# balloon-v02.net
KiCad netlist of a schematic drawn in EAGLE
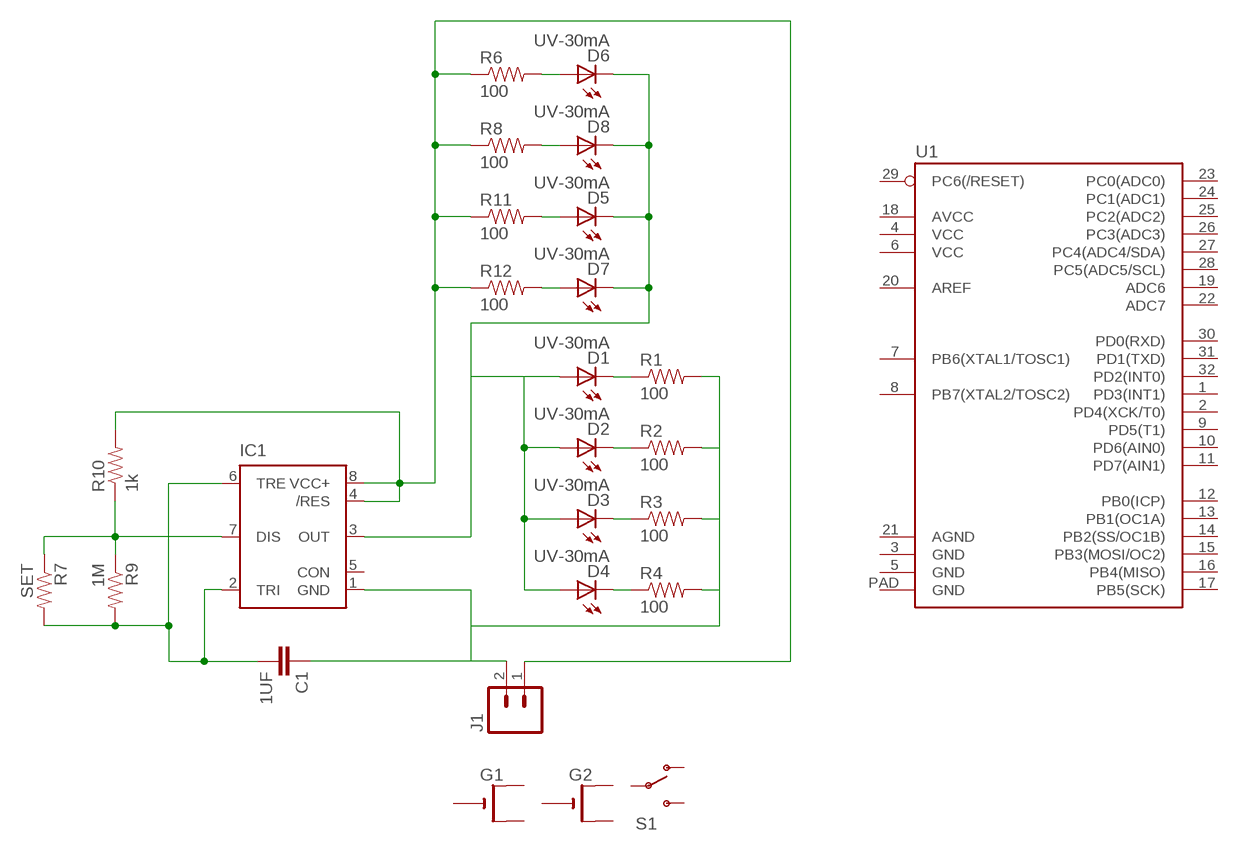
[diagram p0: schematic, sheet 1]

(export (version "E")
  (design (tool "Eeschema 10.0.6"))
  (components
    (comp (ref "C1")
      (value "1UF")
      (footprint "eagle-import:0603-CAP")
      (libsource (lib "eagle-import") (part "CAP0603-CAP"))
    )
    (comp (ref "D1")
      (value "UV-30mA")
      (footprint "eagle-import:CHIPLED_0603")
      (libsource (lib "eagle-import") (part "LEDCHIPLED_0603"))
    )
    (comp (ref "D2")
      (value "UV-30mA")
      (footprint "eagle-import:CHIPLED_0603")
      (libsource (lib "eagle-import") (part "LEDCHIPLED_0603"))
    )
    (comp (ref "D3")
      (value "UV-30mA")
      (footprint "eagle-import:CHIPLED_0603")
      (libsource (lib "eagle-import") (part "LEDCHIPLED_0603"))
    )
    (comp (ref "D4")
      (value "UV-30mA")
      (footprint "eagle-import:CHIPLED_0603")
      (libsource (lib "eagle-import") (part "LEDCHIPLED_0603"))
    )
    (comp (ref "D5")
      (value "UV-30mA")
      (footprint "eagle-import:CHIPLED_0603")
      (libsource (lib "eagle-import") (part "LEDCHIPLED_0603"))
    )
    (comp (ref "D6")
      (value "UV-30mA")
      (footprint "eagle-import:CHIPLED_0603")
      (libsource (lib "eagle-import") (part "LEDCHIPLED_0603"))
    )
    (comp (ref "D7")
      (value "UV-30mA")
      (footprint "eagle-import:CHIPLED_0603")
      (libsource (lib "eagle-import") (part "LEDCHIPLED_0603"))
    )
    (comp (ref "D8")
      (value "UV-30mA")
      (footprint "eagle-import:CHIPLED_0603")
      (libsource (lib "eagle-import") (part "LEDCHIPLED_0603"))
    )
    (comp (ref "G1")
      (value "CR2032SMT")
      (footprint "eagle-import:CR2032-SMD")
      (libsource (lib "eagle-import") (part "CR2032SMT"))
    )
    (comp (ref "G2")
      (value "CR2032SMT")
      (footprint "eagle-import:CR2032-SMD")
      (libsource (lib "eagle-import") (part "CR2032SMT"))
    )
    (comp (ref "IC1")
      (value "NE555D")
      (footprint "eagle-import:SO08")
      (libsource (lib "eagle-import") (part "NE555D"))
    )
    (comp (ref "J1")
      (value "M02PTH3")
      (footprint "eagle-import:1X02_LONGPADS")
      (libsource (lib "eagle-import") (part "M02PTH3"))
    )
    (comp (ref "R1")
      (value "100")
      (footprint "eagle-import:0603-RES")
      (libsource (lib "eagle-import") (part "RESISTOR0603-RES"))
    )
    (comp (ref "R2")
      (value "100")
      (footprint "eagle-import:0603-RES")
      (libsource (lib "eagle-import") (part "RESISTOR0603-RES"))
    )
    (comp (ref "R3")
      (value "100")
      (footprint "eagle-import:0603-RES")
      (libsource (lib "eagle-import") (part "RESISTOR0603-RES"))
    )
    (comp (ref "R4")
      (value "100")
      (footprint "eagle-import:0603-RES")
      (libsource (lib "eagle-import") (part "RESISTOR0603-RES"))
    )
    (comp (ref "R6")
      (value "100")
      (footprint "eagle-import:0603-RES")
      (libsource (lib "eagle-import") (part "RESISTOR0603-RES"))
    )
    (comp (ref "R7")
      (value "SET")
      (footprint "eagle-import:AXIAL-0.3-KIT")
      (libsource (lib "eagle-import") (part "RESISTORKIT"))
    )
    (comp (ref "R8")
      (value "100")
      (footprint "eagle-import:0603-RES")
      (libsource (lib "eagle-import") (part "RESISTOR0603-RES"))
    )
    (comp (ref "R9")
      (value "1M")
      (footprint "eagle-import:0603-RES")
      (libsource (lib "eagle-import") (part "RESISTOR0603-RES"))
    )
    (comp (ref "R10")
      (value "1k")
      (footprint "eagle-import:0603-RES")
      (libsource (lib "eagle-import") (part "RESISTOR0603-RES"))
    )
    (comp (ref "R11")
      (value "100")
      (footprint "eagle-import:0603-RES")
      (libsource (lib "eagle-import") (part "RESISTOR0603-RES"))
    )
    (comp (ref "R12")
      (value "100")
      (footprint "eagle-import:0603-RES")
      (libsource (lib "eagle-import") (part "RESISTOR0603-RES"))
    )
    (comp (ref "S1")
      (value "SWITCH-SPDT-SMD-A")
      (footprint "eagle-import:SWITCH-SPST-SMD-A")
      (libsource (lib "eagle-import") (part "SWITCH-SPDT-SMD-A"))
    )
    (comp (ref "U1")
      (value "ATMEGA328P_MLFMLF32")
      (footprint "eagle-import:MLF32-PAD")
      (libsource (lib "eagle-import") (part "ATMEGA328P_MLFMLF32"))
    )
  )
  (nets
    (net (code "1") (name "Net-(D1-PadC)") (class "Default")
      (node (ref "D1") (pin "C") (pinfunction "C_C") (pintype "passive"))
      (node (ref "R1") (pin "1") (pinfunction "1_1") (pintype "passive"))
    )
    (net (code "2") (name "Net-(D2-PadC)") (class "Default")
      (node (ref "D2") (pin "C") (pinfunction "C_C") (pintype "passive"))
      (node (ref "R2") (pin "1") (pinfunction "1_1") (pintype "passive"))
    )
    (net (code "3") (name "Net-(D3-PadC)") (class "Default")
      (node (ref "D3") (pin "C") (pinfunction "C_C") (pintype "passive"))
      (node (ref "R3") (pin "1") (pinfunction "1_1") (pintype "passive"))
    )
    (net (code "4") (name "Net-(D4-PadC)") (class "Default")
      (node (ref "D4") (pin "C") (pinfunction "C_C") (pintype "passive"))
      (node (ref "R4") (pin "1") (pinfunction "1_1") (pintype "passive"))
    )
    (net (code "5") (name "Net-(D5-PadA)") (class "Default")
      (node (ref "D5") (pin "A") (pinfunction "A_A") (pintype "passive"))
      (node (ref "R11") (pin "2") (pinfunction "2_2") (pintype "passive"))
    )
    (net (code "6") (name "Net-(D6-PadA)") (class "Default")
      (node (ref "D6") (pin "A") (pinfunction "A_A") (pintype "passive"))
      (node (ref "R6") (pin "2") (pinfunction "2_2") (pintype "passive"))
    )
    (net (code "7") (name "Net-(D7-PadA)") (class "Default")
      (node (ref "D7") (pin "A") (pinfunction "A_A") (pintype "passive"))
      (node (ref "R12") (pin "2") (pinfunction "2_2") (pintype "passive"))
    )
    (net (code "8") (name "Net-(D8-PadA)") (class "Default")
      (node (ref "D8") (pin "A") (pinfunction "A_A") (pintype "passive"))
      (node (ref "R8") (pin "2") (pinfunction "2_2") (pintype "passive"))
    )
    (net (code "9") (name "Net-(IC1-DIS)") (class "Default")
      (node (ref "IC1") (pin "7") (pinfunction "DIS_7") (pintype "input"))
      (node (ref "R10") (pin "1") (pinfunction "1_1") (pintype "passive"))
      (node (ref "R7") (pin "P$1") (pinfunction "1_P$1") (pintype "passive"))
      (node (ref "R9") (pin "1") (pinfunction "1_1") (pintype "passive"))
    )
    (net (code "10") (name "Net-(IC1-GND)") (class "Default")
      (node (ref "C1") (pin "1") (pinfunction "1_1") (pintype "passive"))
      (node (ref "IC1") (pin "1") (pinfunction "GND_1") (pintype "power_in"))
      (node (ref "J1") (pin "2") (pinfunction "2_2") (pintype "passive"))
      (node (ref "R1") (pin "2") (pinfunction "2_2") (pintype "passive"))
      (node (ref "R2") (pin "2") (pinfunction "2_2") (pintype "passive"))
      (node (ref "R3") (pin "2") (pinfunction "2_2") (pintype "passive"))
      (node (ref "R4") (pin "2") (pinfunction "2_2") (pintype "passive"))
    )
    (net (code "11") (name "Net-(IC1-OUT)") (class "Default")
      (node (ref "D1") (pin "A") (pinfunction "A_A") (pintype "passive"))
      (node (ref "D2") (pin "A") (pinfunction "A_A") (pintype "passive"))
      (node (ref "D3") (pin "A") (pinfunction "A_A") (pintype "passive"))
      (node (ref "D4") (pin "A") (pinfunction "A_A") (pintype "passive"))
      (node (ref "D5") (pin "C") (pinfunction "C_C") (pintype "passive"))
      (node (ref "D6") (pin "C") (pinfunction "C_C") (pintype "passive"))
      (node (ref "D7") (pin "C") (pinfunction "C_C") (pintype "passive"))
      (node (ref "D8") (pin "C") (pinfunction "C_C") (pintype "passive"))
      (node (ref "IC1") (pin "3") (pinfunction "OUT_3") (pintype "output"))
    )
    (net (code "12") (name "Net-(IC1-TRE)") (class "Default")
      (node (ref "C1") (pin "2") (pinfunction "2_2") (pintype "passive"))
      (node (ref "IC1") (pin "2") (pinfunction "TRI_2") (pintype "input"))
      (node (ref "IC1") (pin "6") (pinfunction "TRE_6") (pintype "input"))
      (node (ref "R7") (pin "P$2") (pinfunction "2_P$2") (pintype "passive"))
      (node (ref "R9") (pin "2") (pinfunction "2_2") (pintype "passive"))
    )
    (net (code "13") (name "Net-(IC1-VCC+)") (class "Default")
      (node (ref "IC1") (pin "4") (pinfunction "/RES_4") (pintype "input"))
      (node (ref "IC1") (pin "8") (pinfunction "VCC+_8") (pintype "power_in"))
      (node (ref "J1") (pin "1") (pinfunction "1_1") (pintype "passive"))
      (node (ref "R10") (pin "2") (pinfunction "2_2") (pintype "passive"))
      (node (ref "R11") (pin "1") (pinfunction "1_1") (pintype "passive"))
      (node (ref "R12") (pin "1") (pinfunction "1_1") (pintype "passive"))
      (node (ref "R6") (pin "1") (pinfunction "1_1") (pintype "passive"))
      (node (ref "R8") (pin "1") (pinfunction "1_1") (pintype "passive"))
    )
    (net (code "14") (name "unconnected-(G1-+-Pad+$1)") (class "Default")
      (node (ref "G1") (pin "+$1") (pinfunction "+_+$1") (pintype "passive"))
    )
    (net (code "15") (name "unconnected-(G1-+1-Pad+$2)") (class "Default")
      (node (ref "G1") (pin "+$2") (pinfunction "+1_+$2") (pintype "passive"))
    )
    (net (code "16") (name "unconnected-(G1-Pad-)") (class "Default")
      (node (ref "G1") (pin "-") (pinfunction "-_-") (pintype "passive"))
    )
    (net (code "17") (name "unconnected-(G2-+-Pad+$1)") (class "Default")
      (node (ref "G2") (pin "+$1") (pinfunction "+_+$1") (pintype "passive"))
    )
    (net (code "18") (name "unconnected-(G2-+1-Pad+$2)") (class "Default")
      (node (ref "G2") (pin "+$2") (pinfunction "+1_+$2") (pintype "passive"))
    )
    (net (code "19") (name "unconnected-(G2-Pad-)") (class "Default")
      (node (ref "G2") (pin "-") (pinfunction "-_-") (pintype "passive"))
    )
    (net (code "20") (name "unconnected-(IC1-CON-Pad5)") (class "Default")
      (node (ref "IC1") (pin "5") (pinfunction "CON_5") (pintype "input"))
    )
    (net (code "21") (name "unconnected-(S1-O-Pad1)") (class "Default")
      (node (ref "S1") (pin "1") (pinfunction "O_1") (pintype "passive"))
    )
    (net (code "22") (name "unconnected-(S1-P-Pad2)") (class "Default")
      (node (ref "S1") (pin "2") (pinfunction "P_2") (pintype "passive"))
    )
    (net (code "23") (name "unconnected-(S1-S-Pad3)") (class "Default")
      (node (ref "S1") (pin "3") (pinfunction "S_3") (pintype "passive"))
    )
    (net (code "24") (name "unconnected-(U1-ADC6-Pad19)") (class "Default")
      (node (ref "U1") (pin "19") (pinfunction "ADC6_19") (pintype "bidirectional"))
    )
    (net (code "25") (name "unconnected-(U1-ADC7-Pad22)") (class "Default")
      (node (ref "U1") (pin "22") (pinfunction "ADC7_22") (pintype "bidirectional"))
    )
    (net (code "26") (name "unconnected-(U1-AGND-Pad21)") (class "Default")
      (node (ref "U1") (pin "21") (pinfunction "AGND_21") (pintype "bidirectional"))
    )
    (net (code "27") (name "unconnected-(U1-AREF-Pad20)") (class "Default")
      (node (ref "U1") (pin "20") (pinfunction "AREF_20") (pintype "bidirectional"))
    )
    (net (code "28") (name "unconnected-(U1-AVCC-Pad18)") (class "Default")
      (node (ref "U1") (pin "18") (pinfunction "AVCC_18") (pintype "bidirectional"))
    )
    (net (code "29") (name "unconnected-(U1-GND-Pad3)") (class "Default")
      (node (ref "U1") (pin "3") (pinfunction "GND_3") (pintype "bidirectional"))
    )
    (net (code "30") (name "unconnected-(U1-GND-Pad5)") (class "Default")
      (node (ref "U1") (pin "5") (pinfunction "GND_5") (pintype "bidirectional"))
    )
    (net (code "31") (name "unconnected-(U1-GND-PadPAD)") (class "Default")
      (node (ref "U1") (pin "PAD") (pinfunction "GND_PAD") (pintype "bidirectional"))
    )
    (net (code "32") (name "unconnected-(U1-PB0(ICP)-Pad12)") (class "Default")
      (node (ref "U1") (pin "12") (pinfunction "PB0(ICP)_12") (pintype "bidirectional"))
    )
    (net (code "33") (name "unconnected-(U1-PB1(OC1A)-Pad13)") (class "Default")
      (node (ref "U1") (pin "13") (pinfunction "PB1(OC1A)_13") (pintype "bidirectional"))
    )
    (net (code "34") (name "unconnected-(U1-PB2(SS{slash}OC1B)-Pad14)") (class "Default")
      (node (ref "U1") (pin "14") (pinfunction "PB2(SS/OC1B)_14") (pintype "bidirectional"))
    )
    (net (code "35") (name "unconnected-(U1-PB3(MOSI{slash}OC2)-Pad15)") (class "Default")
      (node (ref "U1") (pin "15") (pinfunction "PB3(MOSI/OC2)_15") (pintype "bidirectional"))
    )
    (net (code "36") (name "unconnected-(U1-PB4(MISO)-Pad16)") (class "Default")
      (node (ref "U1") (pin "16") (pinfunction "PB4(MISO)_16") (pintype "bidirectional"))
    )
    (net (code "37") (name "unconnected-(U1-PB5(SCK)-Pad17)") (class "Default")
      (node (ref "U1") (pin "17") (pinfunction "PB5(SCK)_17") (pintype "bidirectional"))
    )
    (net (code "38") (name "unconnected-(U1-PB6(XTAL1{slash}TOSC1)-Pad7)") (class "Default")
      (node (ref "U1") (pin "7") (pinfunction "PB6(XTAL1/TOSC1)_7") (pintype "bidirectional"))
    )
    (net (code "39") (name "unconnected-(U1-PB7(XTAL2{slash}TOSC2)-Pad8)") (class "Default")
      (node (ref "U1") (pin "8") (pinfunction "PB7(XTAL2/TOSC2)_8") (pintype "bidirectional"))
    )
    (net (code "40") (name "unconnected-(U1-PC0(ADC0)-Pad23)") (class "Default")
      (node (ref "U1") (pin "23") (pinfunction "PC0(ADC0)_23") (pintype "bidirectional"))
    )
    (net (code "41") (name "unconnected-(U1-PC1(ADC1)-Pad24)") (class "Default")
      (node (ref "U1") (pin "24") (pinfunction "PC1(ADC1)_24") (pintype "bidirectional"))
    )
    (net (code "42") (name "unconnected-(U1-PC2(ADC2)-Pad25)") (class "Default")
      (node (ref "U1") (pin "25") (pinfunction "PC2(ADC2)_25") (pintype "bidirectional"))
    )
    (net (code "43") (name "unconnected-(U1-PC3(ADC3)-Pad26)") (class "Default")
      (node (ref "U1") (pin "26") (pinfunction "PC3(ADC3)_26") (pintype "bidirectional"))
    )
    (net (code "44") (name "unconnected-(U1-PC4(ADC4{slash}SDA)-Pad27)") (class "Default")
      (node (ref "U1") (pin "27") (pinfunction "PC4(ADC4/SDA)_27") (pintype "bidirectional"))
    )
    (net (code "45") (name "unconnected-(U1-PC5(ADC5{slash}SCL)-Pad28)") (class "Default")
      (node (ref "U1") (pin "28") (pinfunction "PC5(ADC5/SCL)_28") (pintype "bidirectional"))
    )
    (net (code "46") (name "unconnected-(U1-PC6({slash}RESET)-Pad29)") (class "Default")
      (node (ref "U1") (pin "29") (pinfunction "PC6(/RESET)_29") (pintype "bidirectional"))
    )
    (net (code "47") (name "unconnected-(U1-PD0(RXD)-Pad30)") (class "Default")
      (node (ref "U1") (pin "30") (pinfunction "PD0(RXD)_30") (pintype "bidirectional"))
    )
    (net (code "48") (name "unconnected-(U1-PD1(TXD)-Pad31)") (class "Default")
      (node (ref "U1") (pin "31") (pinfunction "PD1(TXD)_31") (pintype "bidirectional"))
    )
    (net (code "49") (name "unconnected-(U1-PD2(INT0)-Pad32)") (class "Default")
      (node (ref "U1") (pin "32") (pinfunction "PD2(INT0)_32") (pintype "bidirectional"))
    )
    (net (code "50") (name "unconnected-(U1-PD3(INT1)-Pad1)") (class "Default")
      (node (ref "U1") (pin "1") (pinfunction "PD3(INT1)_1") (pintype "bidirectional"))
    )
    (net (code "51") (name "unconnected-(U1-PD4(XCK{slash}T0)-Pad2)") (class "Default")
      (node (ref "U1") (pin "2") (pinfunction "PD4(XCK/T0)_2") (pintype "bidirectional"))
    )
    (net (code "52") (name "unconnected-(U1-PD5(T1)-Pad9)") (class "Default")
      (node (ref "U1") (pin "9") (pinfunction "PD5(T1)_9") (pintype "bidirectional"))
    )
    (net (code "53") (name "unconnected-(U1-PD6(AIN0)-Pad10)") (class "Default")
      (node (ref "U1") (pin "10") (pinfunction "PD6(AIN0)_10") (pintype "bidirectional"))
    )
    (net (code "54") (name "unconnected-(U1-PD7(AIN1)-Pad11)") (class "Default")
      (node (ref "U1") (pin "11") (pinfunction "PD7(AIN1)_11") (pintype "bidirectional"))
    )
    (net (code "55") (name "unconnected-(U1-VCC-Pad4)") (class "Default")
      (node (ref "U1") (pin "4") (pinfunction "VCC_4") (pintype "bidirectional"))
    )
    (net (code "56") (name "unconnected-(U1-VCC-Pad6)") (class "Default")
      (node (ref "U1") (pin "6") (pinfunction "VCC_6") (pintype "bidirectional"))
    )
  )
)
